# VSENSE_EQ.net
KiCad netlist of a schematic drawn in Altium Designer
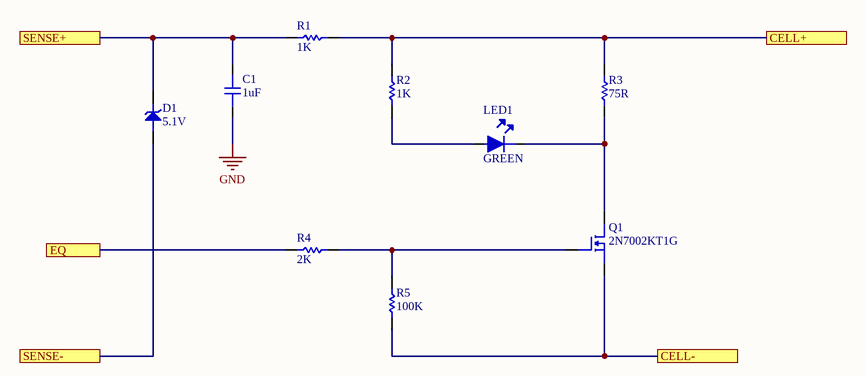
[diagram p0: VSENSE_EQ.SchDoc]

(export (version "E")
  (design (tool "Eeschema 10.0.6"))
  (components
    (comp (ref "C1")
      (value "1uF")
      (footprint "0805 CAP")
      (description "CAP CER 1UF 100V X7S 0805")
      (fields
        (field (name "MANUFACTURER") "TDK")
        (field (name "MANUFACTURER PART NUMBER") "C2012X7S2A105K125AE")
      )
      (libsource (lib "parts") (part "C2012X7S2A105K125AE"))
    )
    (comp (ref "D1")
      (value "5.1V")
      (footprint "ZENER DIODE")
      (description "DIODE ZENER 5.1V 500MW SOD123")
      (fields (field (name "MANUFACTURER") "MCC") (field (name "MANUFACTURER PART NUMBER") "MMSZ4689-TP"))
      (libsource (lib "parts") (part "MMSZ4689-TP"))
    )
    (comp (ref "LED1")
      (value "GREEN")
      (footprint "LED2")
      (description "LED GREEN CLEAR 0603 SMD")
      (fields
        (field (name "MANUFACTURER") "Wurth Electronics")
        (field (name "MANUFACTURER PART NUMBER") "150060VS75000")
      )
      (libsource (lib "parts") (part "150060VS75000"))
    )
    (comp (ref "Q1")
      (value "2N7002KT1G")
      (footprint "N-MOSFET")
      (description "MOSFET N-CH 60V 320MA SOT-23")
      (fields (field (name "MANUFACTURER") "ON Semiconductor"))
      (libsource (lib "parts") (part "2N7002KT1G"))
    )
    (comp (ref "R1")
      (value "1K")
      (footprint "0603 RES")
      (description "RES SMD 1K OHM 1% 1/10W 0603")
      (fields
        (field (name "MANUFACTURER") "Vishay Dale")
        (field (name "MANUFACTURER PART NUMBER") "CRCW06031K00FKEA")
      )
      (libsource (lib "parts") (part "CRCW06031K00FKEA"))
    )
    (comp (ref "R2")
      (value "1K")
      (footprint "0603 RES")
      (description "RES SMD 1K OHM 1% 1/10W 0603")
      (fields
        (field (name "MANUFACTURER") "Vishay Dale")
        (field (name "MANUFACTURER PART NUMBER") "CRCW06031K00FKEA")
      )
      (libsource (lib "parts") (part "CRCW06031K00FKEA"))
    )
    (comp (ref "R3")
      (value "75R")
      (footprint "2512 RES")
      (description "RES 75 OHM 1% 1W 2512")
      (fields
        (field (name "MANUFACTURER") "Stackpole Electronics")
        (field (name "MANUFACTURER PART NUMBER") "RMCF2512FT75R0")
      )
      (libsource (lib "parts") (part "RMCF2512FT75R0"))
    )
    (comp (ref "R4")
      (value "2K")
      (footprint "0603 RES")
      (description "RES SMD 2K OHM 1% 1/10W 0603")
      (fields
        (field (name "MANUFACTURER") "Vishay")
        (field (name "MANUFACTURER PART NUMBER") "CRCW06032K00FKEA")
      )
      (libsource (lib "parts") (part "CRCW06032K00FKEA"))
    )
    (comp (ref "R5")
      (value "100K")
      (footprint "0603 RES")
      (description "RES SMD 100K OHM 1% 1/10W 0603")
      (fields
        (field (name "MANUFACTURER") "Panasonic")
        (field (name "MANUFACTURER PART NUMBER") "ERJ3EKF-1003V")
      )
      (libsource (lib "parts") (part "ERJ-3EKF1003V"))
    )
  )
  (nets
    (net (code "1") (name "/CELL+") (class "Default")
      (node (ref "R1") (pin "2") (pinfunction "2_2") (pintype "passive"))
      (node (ref "R2") (pin "2") (pinfunction "2_2") (pintype "passive"))
      (node (ref "R3") (pin "1") (pinfunction "1_1") (pintype "passive"))
    )
    (net (code "2") (name "/CELL-") (class "Default")
      (node (ref "Q1") (pin "2") (pinfunction "2_2") (pintype "passive"))
      (node (ref "R5") (pin "1") (pinfunction "1_1") (pintype "passive"))
    )
    (net (code "3") (name "/EQ") (class "Default")
      (node (ref "R4") (pin "1") (pinfunction "1_1") (pintype "passive"))
    )
    (net (code "4") (name "/SENSE+") (class "Default")
      (node (ref "C1") (pin "2") (pinfunction "2_2") (pintype "passive"))
      (node (ref "D1") (pin "2") (pinfunction "2_2") (pintype "passive"))
      (node (ref "R1") (pin "1") (pinfunction "1_1") (pintype "passive"))
    )
    (net (code "5") (name "/SENSE-") (class "Default")
      (node (ref "D1") (pin "1") (pinfunction "1_1") (pintype "passive"))
    )
    (net (code "6") (name "GND") (class "Default")
      (node (ref "C1") (pin "1") (pinfunction "1_1") (pintype "passive"))
    )
    (net (code "7") (name "Net-(LED1-Pad1)") (class "Default")
      (node (ref "LED1") (pin "1") (pinfunction "1_1") (pintype "passive"))
      (node (ref "R2") (pin "1") (pinfunction "1_1") (pintype "passive"))
    )
    (net (code "8") (name "Net-(LED1-Pad2)") (class "Default")
      (node (ref "LED1") (pin "2") (pinfunction "2_2") (pintype "passive"))
      (node (ref "Q1") (pin "3") (pinfunction "3_3") (pintype "passive"))
      (node (ref "R3") (pin "2") (pinfunction "2_2") (pintype "passive"))
    )
    (net (code "9") (name "Net-(Q1-Pad1)") (class "Default")
      (node (ref "Q1") (pin "1") (pinfunction "1_1") (pintype "passive"))
      (node (ref "R4") (pin "2") (pinfunction "2_2") (pintype "passive"))
      (node (ref "R5") (pin "2") (pinfunction "2_2") (pintype "passive"))
    )
  )
)
